# VFD_LCD.net
KiCad netlist of a schematic drawn in Altium Designer
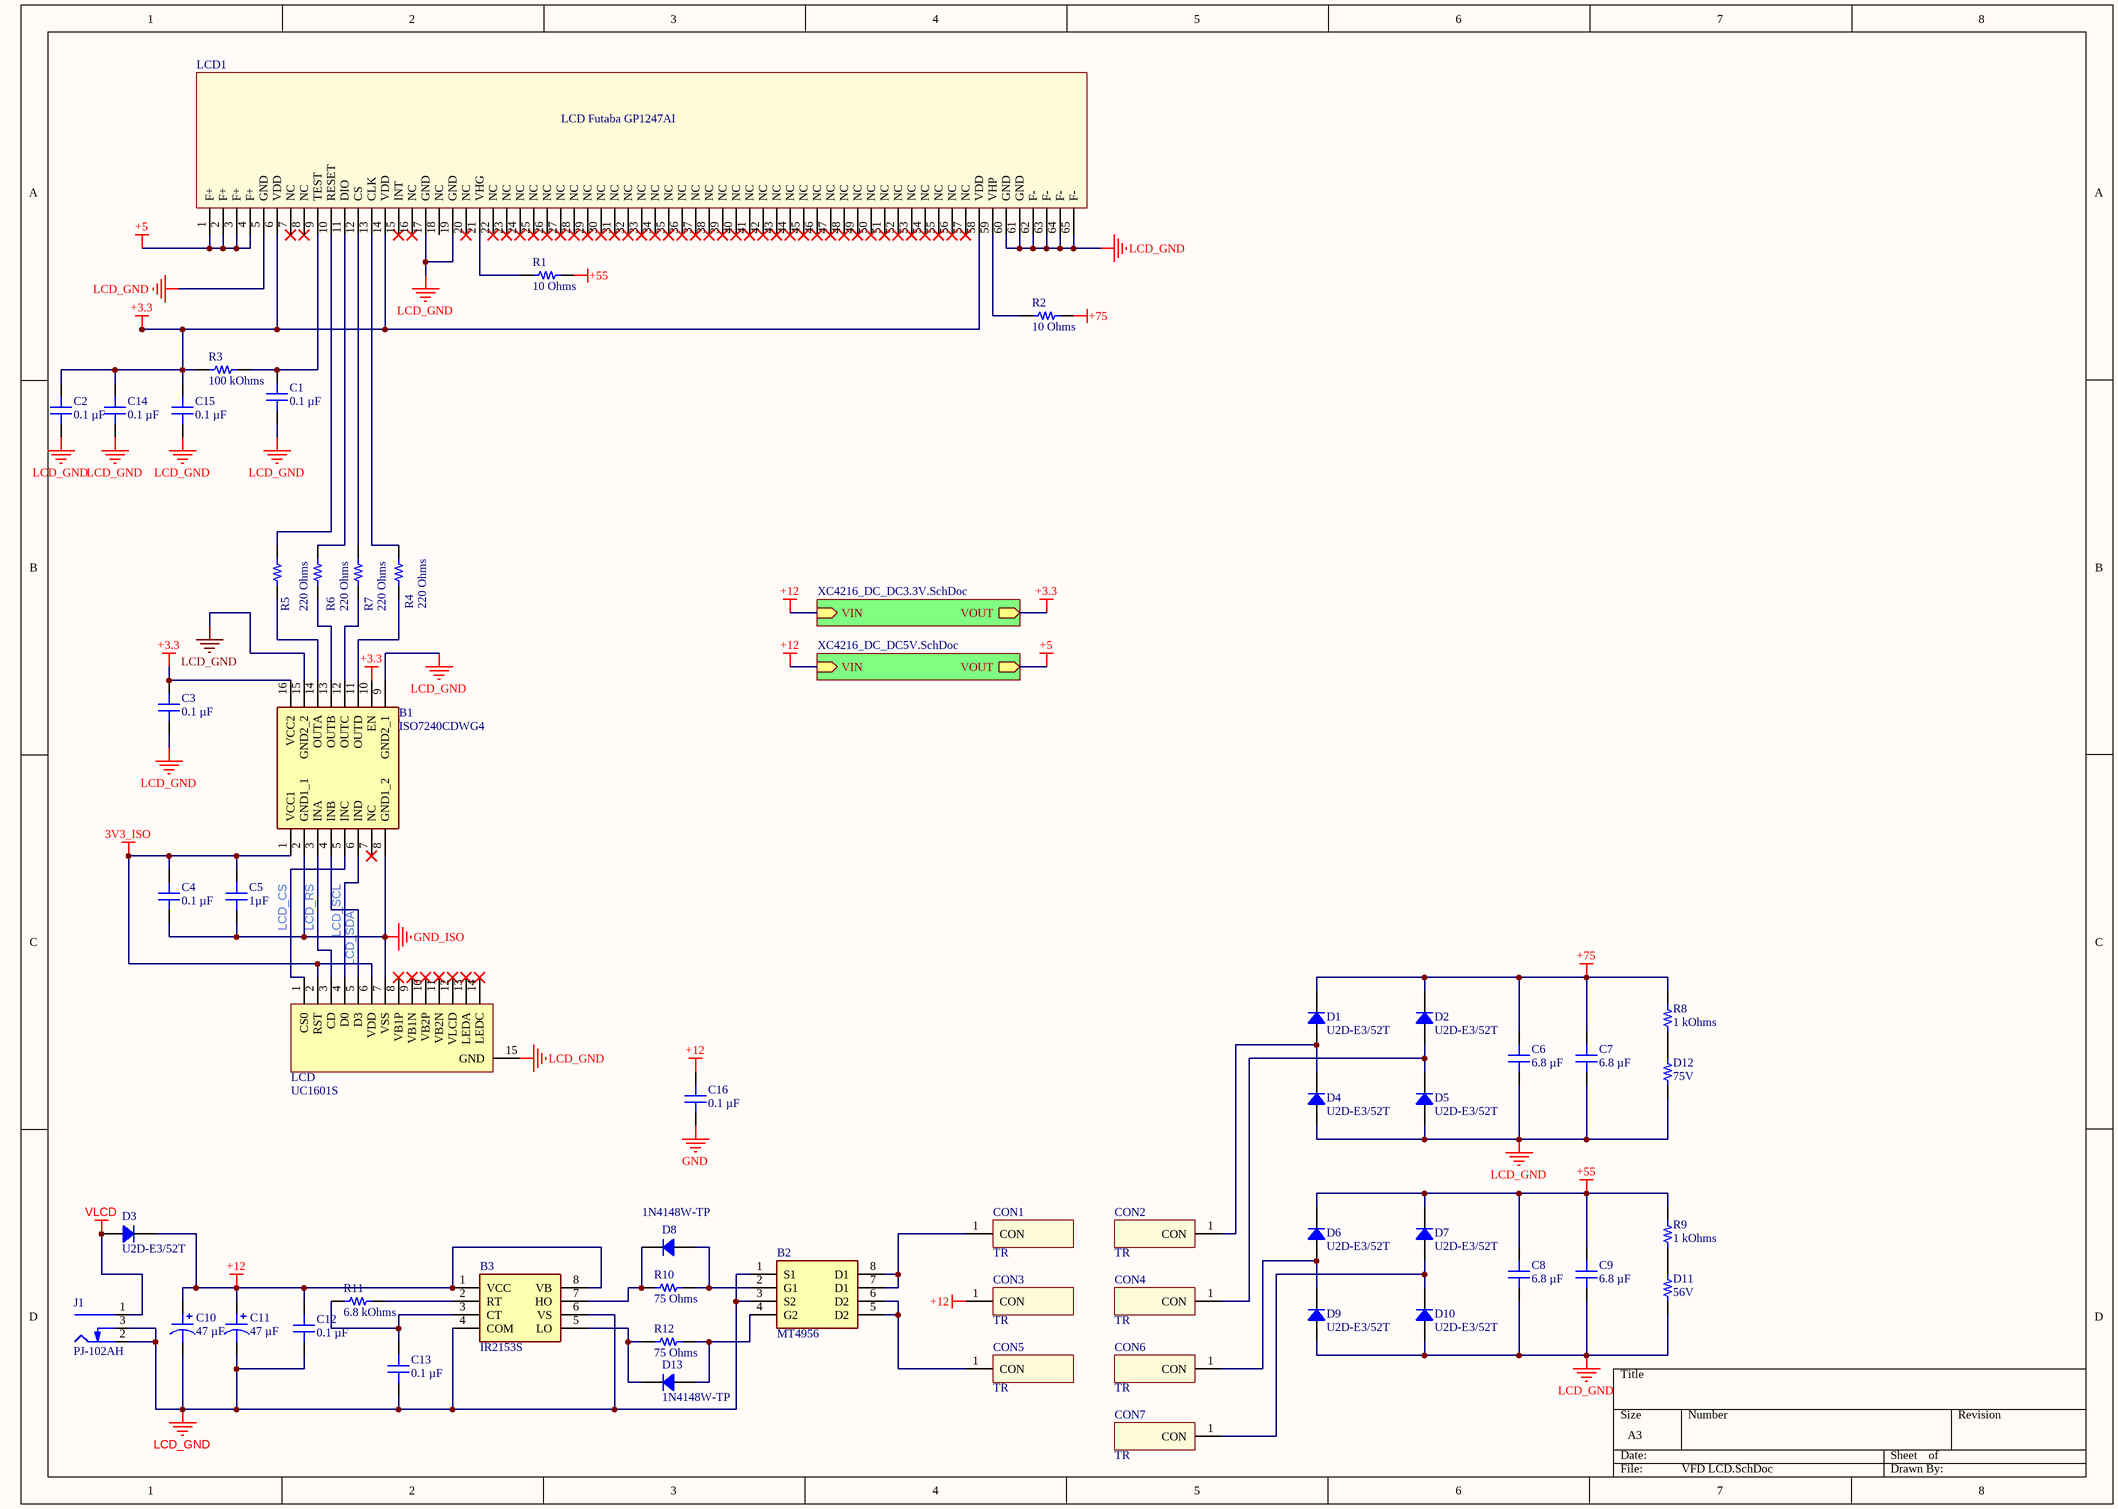
[diagram p0: VFD LCD.SchDoc]

(export (version "E")
  (design (tool "Eeschema 10.0.6"))
  (components
    (comp (ref "B1")
      (value "ISO7240CDWG4")
      (footprint "SOIC127P1030X265-16N")
      (description "Digital Isolator CMOS 4-CH 25Mbps 16-Pin SOIC Tube")
      (fields (field (name "MOUSER PART NUMBER") "595-ISO7240CDWG4"))
      (libsource (lib "My altlib") (part "ISO7240CDWG4"))
    )
    (comp (ref "B2")
      (value "MT4956")
      (footprint "SOIC127P600X175-8N")
      (description "N-Channel PowerTrench® MOSFET\r\n60V, 5A, mΩ")
      (fields (field (name "MANUFACTURER_PART_NUMBER") "IR2153S"))
      (libsource (lib "My altlib") (part "MT4956"))
    )
    (comp (ref "B3")
      (value "IR2153S")
      (footprint "SOIC127P600X175-8N")
      (libsource (lib "My altlib") (part "IR2153S"))
    )
    (comp (ref "C1")
      (value "0.1 µF")
      (footprint "CAP 0805_2012")
      (description "CAP CER 0.1UF 50V X7R 0805")
      (fields (field (name "PART NUMBER") "CC0805MRX7R9BB104") (field (name "MANUFACTURER") "Yageo"))
      (libsource (lib "Celestial Altium Library - altium_library") (part "Capacitor"))
    )
    (comp (ref "C2")
      (value "0.1 µF")
      (footprint "CAP 0805_2012")
      (description "CAP CER 0.1UF 50V X7R 0805")
      (fields (field (name "PART NUMBER") "CC0805MRX7R9BB104") (field (name "MANUFACTURER") "Yageo"))
      (libsource (lib "Celestial Altium Library - altium_library") (part "Capacitor"))
    )
    (comp (ref "C3")
      (value "0.1 µF")
      (footprint "CAP 0805_2012")
      (description "CAP CER 0.1UF 50V X7R 0805")
      (fields (field (name "PART NUMBER") "CC0805MRX7R9BB104") (field (name "MANUFACTURER") "Yageo"))
      (libsource (lib "Celestial Altium Library - altium_library") (part "Capacitor"))
    )
    (comp (ref "C4")
      (value "0.1 µF")
      (footprint "CAP 0805_2012")
      (description "CAP CER 0.1UF 50V X7R 0805")
      (fields (field (name "PART NUMBER") "CC0805MRX7R9BB104") (field (name "MANUFACTURER") "Yageo"))
      (libsource (lib "Celestial Altium Library - altium_library") (part "Capacitor"))
    )
    (comp (ref "C5")
      (value "1µF")
      (footprint "CAP 0805_2012")
      (description "CAP CER 1UF 10V X7R 0805")
      (fields (field (name "PART NUMBER") "MM05ZC105KCZ2A") (field (name "MANUFACTURER") "AVX Corporation"))
      (libsource (lib "Celestial Altium Library - altium_library") (part "Capacitor"))
    )
    (comp (ref "C6")
      (value "6.8 µF")
      (footprint "CAP 1210_3225 - 1MM")
      (description "CAP CER 6.8UF 50V X7S 1210")
      (fields
        (field (name "PART NUMBER") "CGA6P3X7S1H685K250AB")
        (field (name "MANUFACTURER") "TDK Corporation")
      )
      (libsource (lib "Celestial Altium Library - altium_library") (part "Capacitor"))
    )
    (comp (ref "C7")
      (value "6.8 µF")
      (footprint "CAP 1210_3225 - 1MM")
      (description "CAP CER 6.8UF 50V X7S 1210")
      (fields
        (field (name "PART NUMBER") "CGA6P3X7S1H685K250AB")
        (field (name "MANUFACTURER") "TDK Corporation")
      )
      (libsource (lib "Celestial Altium Library - altium_library") (part "Capacitor"))
    )
    (comp (ref "C8")
      (value "6.8 µF")
      (footprint "CAP 1210_3225 - 1MM")
      (description "CAP CER 6.8UF 50V X7S 1210")
      (fields
        (field (name "PART NUMBER") "CGA6P3X7S1H685K250AB")
        (field (name "MANUFACTURER") "TDK Corporation")
      )
      (libsource (lib "Celestial Altium Library - altium_library") (part "Capacitor"))
    )
    (comp (ref "C9")
      (value "6.8 µF")
      (footprint "CAP 1210_3225 - 1MM")
      (description "CAP CER 6.8UF 50V X7S 1210")
      (fields
        (field (name "PART NUMBER") "CGA6P3X7S1H685K250AB")
        (field (name "MANUFACTURER") "TDK Corporation")
      )
      (libsource (lib "Celestial Altium Library - altium_library") (part "Capacitor"))
    )
    (comp (ref "C10")
      (value "47 µF")
      (footprint "CAP ALSMD 8.3MM H10.5MM")
      (description "CAP ALUM 47UF 20% 63V SMD")
      (fields (field (name "PART NUMBER") "63SGV47M8X10.5") (field (name "MANUFACTURER") "Rubycon"))
      (libsource (lib "Celestial Altium Library - altium_library") (part "Polarised Capacitor"))
    )
    (comp (ref "C11")
      (value "47 µF")
      (footprint "CAP ALSMD 8.3MM H10.5MM")
      (description "CAP ALUM 47UF 20% 63V SMD")
      (fields (field (name "PART NUMBER") "63SGV47M8X10.5") (field (name "MANUFACTURER") "Rubycon"))
      (libsource (lib "Celestial Altium Library - altium_library") (part "Polarised Capacitor"))
    )
    (comp (ref "C12")
      (value "0.1 µF")
      (footprint "CAP 1206_3216 - 0.8MM")
      (description "CAP CER 0.1UF 50V Y5V 1206")
      (fields (field (name "PART NUMBER") "CC1206MRY5V9BB104") (field (name "MANUFACTURER") "Yageo"))
      (libsource (lib "Celestial Altium Library - altium_library") (part "Capacitor"))
    )
    (comp (ref "C13")
      (value "0.1 µF")
      (footprint "CAP 1206_3216 - 0.8MM")
      (description "CAP CER 0.1UF 50V Y5V 1206")
      (fields (field (name "PART NUMBER") "CC1206MRY5V9BB104") (field (name "MANUFACTURER") "Yageo"))
      (libsource (lib "Celestial Altium Library - altium_library") (part "Capacitor"))
    )
    (comp (ref "C14")
      (value "0.1 µF")
      (footprint "CAP 0805_2012")
      (description "CAP CER 0.1UF 50V X7R 0805")
      (fields (field (name "PART NUMBER") "CC0805MRX7R9BB104") (field (name "MANUFACTURER") "Yageo"))
      (libsource (lib "Celestial Altium Library - altium_library") (part "Capacitor"))
    )
    (comp (ref "C15")
      (value "0.1 µF")
      (footprint "CAP 0805_2012")
      (description "CAP CER 0.1UF 50V X7R 0805")
      (fields (field (name "PART NUMBER") "CC0805MRX7R9BB104") (field (name "MANUFACTURER") "Yageo"))
      (libsource (lib "Celestial Altium Library - altium_library") (part "Capacitor"))
    )
    (comp (ref "C16")
      (value "0.1 µF")
      (footprint "CAP 1206_3216 - 0.8MM")
      (description "CAP CER 0.1UF 50V Y5V 1206")
      (fields (field (name "PART NUMBER") "CC1206MRY5V9BB104") (field (name "MANUFACTURER") "Yageo"))
      (libsource (lib "Celestial Altium Library - altium_library") (part "Capacitor"))
    )
    (comp (ref "CON1")
      (value "TR")
      (footprint "one contact 0,8_1.6")
      (description "ONE_Contact")
      (libsource (lib "") (part "ONE_Contact_1"))
    )
    (comp (ref "CON2")
      (value "TR")
      (footprint "one contact 0,8_1.6")
      (description "ONE_Contact")
      (libsource (lib "My altlib") (part "ONE_Contact"))
    )
    (comp (ref "CON3")
      (value "TR")
      (footprint "one contact 0,8_1.6")
      (description "ONE_Contact")
      (libsource (lib "") (part "ONE_Contact_1"))
    )
    (comp (ref "CON4")
      (value "TR")
      (footprint "one contact 0,8_1.6")
      (description "ONE_Contact")
      (libsource (lib "My altlib") (part "ONE_Contact"))
    )
    (comp (ref "CON5")
      (value "TR")
      (footprint "one contact 0,8_1.6")
      (description "ONE_Contact")
      (libsource (lib "") (part "ONE_Contact_1"))
    )
    (comp (ref "CON6")
      (value "TR")
      (footprint "one contact 0,8_1.6")
      (description "ONE_Contact")
      (libsource (lib "My altlib") (part "ONE_Contact"))
    )
    (comp (ref "CON7")
      (value "TR")
      (footprint "one contact 0,8_1.6")
      (description "ONE_Contact")
      (libsource (lib "My altlib") (part "ONE_Contact"))
    )
    (comp (ref "D1")
      (value "U2D-E3/52T")
      (footprint "DO214AA SMB")
      (description "DIODE GEN PURP 200V 2A DO214AA")
      (fields (field (name "MANUFACTURER") "Vishay Semiconductor Diodes Division"))
      (libsource (lib "Celestial Altium Library - altium_library") (part "Diode"))
    )
    (comp (ref "D2")
      (value "U2D-E3/52T")
      (footprint "DO214AA SMB")
      (description "DIODE GEN PURP 200V 2A DO214AA")
      (fields (field (name "MANUFACTURER") "Vishay Semiconductor Diodes Division"))
      (libsource (lib "Celestial Altium Library - altium_library") (part "Diode"))
    )
    (comp (ref "D3")
      (value "U2D-E3/52T")
      (footprint "DO214AA SMB")
      (description "DIODE GEN PURP 200V 2A DO214AA")
      (fields (field (name "MANUFACTURER") "Vishay Semiconductor Diodes Division"))
      (libsource (lib "Celestial Altium Library - altium_library") (part "Diode"))
    )
    (comp (ref "D4")
      (value "U2D-E3/52T")
      (footprint "DO214AA SMB")
      (description "DIODE GEN PURP 200V 2A DO214AA")
      (fields (field (name "MANUFACTURER") "Vishay Semiconductor Diodes Division"))
      (libsource (lib "Celestial Altium Library - altium_library") (part "Diode"))
    )
    (comp (ref "D5")
      (value "U2D-E3/52T")
      (footprint "DO214AA SMB")
      (description "DIODE GEN PURP 200V 2A DO214AA")
      (fields (field (name "MANUFACTURER") "Vishay Semiconductor Diodes Division"))
      (libsource (lib "Celestial Altium Library - altium_library") (part "Diode"))
    )
    (comp (ref "D6")
      (value "U2D-E3/52T")
      (footprint "DO214AA SMB")
      (description "DIODE GEN PURP 200V 2A DO214AA")
      (fields (field (name "MANUFACTURER") "Vishay Semiconductor Diodes Division"))
      (libsource (lib "Celestial Altium Library - altium_library") (part "Diode"))
    )
    (comp (ref "D7")
      (value "U2D-E3/52T")
      (footprint "DO214AA SMB")
      (description "DIODE GEN PURP 200V 2A DO214AA")
      (fields (field (name "MANUFACTURER") "Vishay Semiconductor Diodes Division"))
      (libsource (lib "Celestial Altium Library - altium_library") (part "Diode"))
    )
    (comp (ref "D8")
      (value "1N4148W-TP")
      (footprint "SOD-123")
      (description "DIODE GEN PURP 100V 150MA SOD123")
      (fields (field (name "MANUFACTURER") "Micro Commercial Co"))
      (libsource (lib "Celestial Altium Library - altium_library") (part "Diode"))
    )
    (comp (ref "D9")
      (value "U2D-E3/52T")
      (footprint "DO214AA SMB")
      (description "DIODE GEN PURP 200V 2A DO214AA")
      (fields (field (name "MANUFACTURER") "Vishay Semiconductor Diodes Division"))
      (libsource (lib "Celestial Altium Library - altium_library") (part "Diode"))
    )
    (comp (ref "D10")
      (value "U2D-E3/52T")
      (footprint "DO214AA SMB")
      (description "DIODE GEN PURP 200V 2A DO214AA")
      (fields (field (name "MANUFACTURER") "Vishay Semiconductor Diodes Division"))
      (libsource (lib "Celestial Altium Library - altium_library") (part "Diode"))
    )
    (comp (ref "D11")
      (value "56V")
      (footprint "RES 1206_3216")
      (description "RES 1K OHM 0.1% 1/8W 1206")
      (fields
        (field (name "PART NUMBER") "RNCS1206BKE1K00")
        (field (name "MANUFACTURER") "Stackpole Electronics Inc")
      )
      (libsource (lib "Celestial Altium Library - altium_library") (part "Resistor"))
    )
    (comp (ref "D12")
      (value "75V")
      (footprint "RES 1206_3216")
      (description "RES 1K OHM 0.1% 1/8W 1206")
      (fields
        (field (name "PART NUMBER") "RNCS1206BKE1K00")
        (field (name "MANUFACTURER") "Stackpole Electronics Inc")
      )
      (libsource (lib "Celestial Altium Library - altium_library") (part "Resistor"))
    )
    (comp (ref "D13")
      (value "1N4148W-TP")
      (footprint "SOD-123")
      (description "DIODE GEN PURP 100V 150MA SOD123")
      (fields (field (name "MANUFACTURER") "Micro Commercial Co"))
      (libsource (lib "Celestial Altium Library - altium_library") (part "Diode"))
    )
    (comp (ref "J1")
      (value "PJ-102AH")
      (footprint "CUI PJ-102AH")
      (description "CONN PWR JACK 2X5.5MM SOLDER")
      (fields (field (name "MANUFACTURER") "CUI Devices"))
      (libsource (lib "Celestial Altium Library - altium_library") (part "Barrel Connector"))
    )
    (comp (ref "LCD")
      (value "UC1601S")
      (footprint "FPC0514")
      (description "LCD 65*132")
      (libsource (lib "Mylib") (part "UC1601S"))
    )
    (comp (ref "LCD1")
      (value "GP1247AI")
      (footprint "GP1247AI")
      (libsource (lib "My altlib") (part "GP1247AI"))
    )
    (comp (ref "R1")
      (value "10 Ohms")
      (footprint "RES 1206_3216")
      (description "RES 10 OHM 0.1% 1/8W 1206")
      (fields
        (field (name "PART NUMBER") "RNCS1206BKE10R0")
        (field (name "MANUFACTURER") "Stackpole Electronics Inc")
      )
      (libsource (lib "Celestial Altium Library - altium_library") (part "Resistor"))
    )
    (comp (ref "R2")
      (value "10 Ohms")
      (footprint "RES 1206_3216")
      (description "RES 10 OHM 0.1% 1/8W 1206")
      (fields
        (field (name "PART NUMBER") "RNCS1206BKE10R0")
        (field (name "MANUFACTURER") "Stackpole Electronics Inc")
      )
      (libsource (lib "Celestial Altium Library - altium_library") (part "Resistor"))
    )
    (comp (ref "R3")
      (value "100 kOhms")
      (footprint "RES 0805_2012")
      (description "RES SMD 100K OHM 0.1% 1/10W 0805")
      (fields
        (field (name "PART NUMBER") "CPF0805B100KE")
        (field (name "MANUFACTURER") "TE Connectivity Passive Product")
      )
      (libsource (lib "Celestial Altium Library - altium_library") (part "Resistor"))
    )
    (comp (ref "R4")
      (value "220 Ohms")
      (footprint "RES 0805_2012")
      (description "RES 220 OHM 1% 1/3W 0805")
      (fields
        (field (name "PART NUMBER") "CRGP0805F220R")
        (field (name "MANUFACTURER") "TE Connectivity Passive Product")
      )
      (libsource (lib "Celestial Altium Library - altium_library") (part "Resistor"))
    )
    (comp (ref "R5")
      (value "220 Ohms")
      (footprint "RES 0805_2012")
      (description "RES 220 OHM 1% 1/3W 0805")
      (fields
        (field (name "PART NUMBER") "CRGP0805F220R")
        (field (name "MANUFACTURER") "TE Connectivity Passive Product")
      )
      (libsource (lib "Celestial Altium Library - altium_library") (part "Resistor"))
    )
    (comp (ref "R6")
      (value "220 Ohms")
      (footprint "RES 0805_2012")
      (description "RES 220 OHM 1% 1/3W 0805")
      (fields
        (field (name "PART NUMBER") "CRGP0805F220R")
        (field (name "MANUFACTURER") "TE Connectivity Passive Product")
      )
      (libsource (lib "Celestial Altium Library - altium_library") (part "Resistor"))
    )
    (comp (ref "R7")
      (value "220 Ohms")
      (footprint "RES 0805_2012")
      (description "RES 220 OHM 1% 1/3W 0805")
      (fields
        (field (name "PART NUMBER") "CRGP0805F220R")
        (field (name "MANUFACTURER") "TE Connectivity Passive Product")
      )
      (libsource (lib "Celestial Altium Library - altium_library") (part "Resistor"))
    )
    (comp (ref "R8")
      (value "1 kOhms")
      (footprint "RES 1206_3216")
      (description "RES 1K OHM 0.1% 1/8W 1206")
      (fields
        (field (name "PART NUMBER") "RNCS1206BKE1K00")
        (field (name "MANUFACTURER") "Stackpole Electronics Inc")
      )
      (libsource (lib "Celestial Altium Library - altium_library") (part "Resistor"))
    )
    (comp (ref "R9")
      (value "1 kOhms")
      (footprint "RES 1206_3216")
      (description "RES 1K OHM 0.1% 1/8W 1206")
      (fields
        (field (name "PART NUMBER") "RNCS1206BKE1K00")
        (field (name "MANUFACTURER") "Stackpole Electronics Inc")
      )
      (libsource (lib "Celestial Altium Library - altium_library") (part "Resistor"))
    )
    (comp (ref "R10")
      (value "75 Ohms")
      (footprint "RES 0805_2012")
      (description "RES SMD 7.5 OHM 0.1% 1/10W 0805")
      (fields
        (field (name "PART NUMBER") "CPF0805B7R5E1")
        (field (name "MANUFACTURER") "TE Connectivity Passive Product")
      )
      (libsource (lib "Celestial Altium Library - altium_library") (part "Resistor"))
    )
    (comp (ref "R11")
      (value "6.8 kOhms")
      (footprint "RES 1206_3216")
      (description "RES SMD 6.8K OHM 0.05% 1/4W 1206")
      (fields
        (field (name "PART NUMBER") "ERA-8ARW682V")
        (field (name "MANUFACTURER") "Panasonic Electronic Components")
      )
      (libsource (lib "Celestial Altium Library - altium_library") (part "Resistor"))
    )
    (comp (ref "R12")
      (value "75 Ohms")
      (footprint "RES 0805_2012")
      (description "RES SMD 7.5 OHM 0.1% 1/10W 0805")
      (fields
        (field (name "PART NUMBER") "CPF0805B7R5E1")
        (field (name "MANUFACTURER") "TE Connectivity Passive Product")
      )
      (libsource (lib "Celestial Altium Library - altium_library") (part "Resistor"))
    )
  )
  (nets
    (net (code "1") (name "+3.3") (class "Default")
      (node (ref "B1") (pin "10") (pinfunction "EN_10") (pintype "passive"))
      (node (ref "B1") (pin "16") (pinfunction "VCC2_16") (pintype "passive"))
      (node (ref "C14") (pin "2") (pinfunction "2_2") (pintype "passive"))
      (node (ref "C15") (pin "2") (pinfunction "2_2") (pintype "passive"))
      (node (ref "C2") (pin "2") (pinfunction "2_2") (pintype "passive"))
      (node (ref "C3") (pin "1") (pinfunction "1_1") (pintype "passive"))
      (node (ref "LCD1") (pin "14") (pinfunction "VDD_14") (pintype "passive"))
      (node (ref "LCD1") (pin "58") (pinfunction "VDD_58") (pintype "passive"))
      (node (ref "LCD1") (pin "6") (pinfunction "VDD_6") (pintype "passive"))
      (node (ref "R3") (pin "1") (pinfunction "1_1") (pintype "passive"))
    )
    (net (code "2") (name "+5") (class "Default")
      (node (ref "LCD1") (pin "1") (pinfunction "F+_1") (pintype "passive"))
      (node (ref "LCD1") (pin "2") (pinfunction "F+_2") (pintype "passive"))
      (node (ref "LCD1") (pin "3") (pinfunction "F+_3") (pintype "passive"))
      (node (ref "LCD1") (pin "4") (pinfunction "F+_4") (pintype "passive"))
    )
    (net (code "3") (name "+12") (class "Default")
      (node (ref "B3") (pin "1") (pinfunction "VCC_1") (pintype "passive"))
      (node (ref "B3") (pin "8") (pinfunction "VB_8") (pintype "passive"))
      (node (ref "C10") (pin "1") (pinfunction "1_1") (pintype "passive"))
      (node (ref "C11") (pin "1") (pinfunction "1_1") (pintype "passive"))
      (node (ref "C12") (pin "2") (pinfunction "2_2") (pintype "passive"))
      (node (ref "C16") (pin "2") (pinfunction "2_2") (pintype "passive"))
      (node (ref "CON3") (pin "1") (pinfunction "CON_1") (pintype "passive"))
      (node (ref "D3") (pin "2") (pinfunction "2_2") (pintype "passive"))
    )
    (net (code "4") (name "+55") (class "Default")
      (node (ref "C8") (pin "2") (pinfunction "2_2") (pintype "passive"))
      (node (ref "C9") (pin "2") (pinfunction "2_2") (pintype "passive"))
      (node (ref "D6") (pin "2") (pinfunction "2_2") (pintype "passive"))
      (node (ref "D7") (pin "2") (pinfunction "2_2") (pintype "passive"))
      (node (ref "R1") (pin "2") (pinfunction "2_2") (pintype "passive"))
      (node (ref "R9") (pin "2") (pinfunction "2_2") (pintype "passive"))
    )
    (net (code "5") (name "+75") (class "Default")
      (node (ref "C6") (pin "2") (pinfunction "2_2") (pintype "passive"))
      (node (ref "C7") (pin "2") (pinfunction "2_2") (pintype "passive"))
      (node (ref "D1") (pin "2") (pinfunction "2_2") (pintype "passive"))
      (node (ref "D2") (pin "2") (pinfunction "2_2") (pintype "passive"))
      (node (ref "R2") (pin "2") (pinfunction "2_2") (pintype "passive"))
      (node (ref "R8") (pin "2") (pinfunction "2_2") (pintype "passive"))
    )
    (net (code "6") (name "/LCD_CS") (class "Default")
      (node (ref "B1") (pin "5") (pinfunction "INC_5") (pintype "passive"))
      (node (ref "LCD") (pin "1") (pinfunction "CS0_1") (pintype "passive"))
    )
    (net (code "7") (name "/LCD_RS") (class "Default")
      (node (ref "B1") (pin "3") (pinfunction "INA_3") (pintype "passive"))
      (node (ref "LCD") (pin "3") (pinfunction "CD_3") (pintype "passive"))
    )
    (net (code "8") (name "/LCD_SCL") (class "Default")
      (node (ref "B1") (pin "6") (pinfunction "IND_6") (pintype "passive"))
      (node (ref "LCD") (pin "4") (pinfunction "D0_4") (pintype "passive"))
    )
    (net (code "9") (name "/LCD_SDA") (class "Default")
      (node (ref "B1") (pin "4") (pinfunction "INB_4") (pintype "passive"))
      (node (ref "LCD") (pin "5") (pinfunction "D3_5") (pintype "passive"))
    )
    (net (code "10") (name "3V3_ISO") (class "Default")
      (node (ref "B1") (pin "1") (pinfunction "VCC1_1") (pintype "passive"))
      (node (ref "C4") (pin "1") (pinfunction "1_1") (pintype "passive"))
      (node (ref "C5") (pin "2") (pinfunction "2_2") (pintype "passive"))
      (node (ref "LCD") (pin "2") (pinfunction "RST_2") (pintype "passive"))
      (node (ref "LCD") (pin "6") (pinfunction "VDD_6") (pintype "passive"))
    )
    (net (code "11") (name "GND") (class "Default")
      (node (ref "C16") (pin "1") (pinfunction "1_1") (pintype "passive"))
    )
    (net (code "12") (name "GND_ISO") (class "Default")
      (node (ref "B1") (pin "2") (pinfunction "GND1_1_2") (pintype "passive"))
      (node (ref "B1") (pin "8") (pinfunction "GND1_2_8") (pintype "passive"))
      (node (ref "C4") (pin "2") (pinfunction "2_2") (pintype "passive"))
      (node (ref "C5") (pin "1") (pinfunction "1_1") (pintype "passive"))
      (node (ref "LCD") (pin "7") (pinfunction "VSS_7") (pintype "passive"))
    )
    (net (code "13") (name "LCD_GND") (class "Default")
      (node (ref "B1") (pin "15") (pinfunction "GND2_2_15") (pintype "passive"))
      (node (ref "B1") (pin "9") (pinfunction "GND2_1_9") (pintype "passive"))
      (node (ref "B2") (pin "1") (pinfunction "S1_1") (pintype "passive"))
      (node (ref "B2") (pin "3") (pinfunction "S2_3") (pintype "passive"))
      (node (ref "B3") (pin "4") (pinfunction "COM_4") (pintype "passive"))
      (node (ref "B3") (pin "6") (pinfunction "VS_6") (pintype "passive"))
      (node (ref "C1") (pin "1") (pinfunction "1_1") (pintype "passive"))
      (node (ref "C10") (pin "2") (pinfunction "2_2") (pintype "passive"))
      (node (ref "C11") (pin "2") (pinfunction "2_2") (pintype "passive"))
      (node (ref "C12") (pin "1") (pinfunction "1_1") (pintype "passive"))
      (node (ref "C13") (pin "1") (pinfunction "1_1") (pintype "passive"))
      (node (ref "C14") (pin "1") (pinfunction "1_1") (pintype "passive"))
      (node (ref "C15") (pin "1") (pinfunction "1_1") (pintype "passive"))
      (node (ref "C2") (pin "1") (pinfunction "1_1") (pintype "passive"))
      (node (ref "C3") (pin "2") (pinfunction "2_2") (pintype "passive"))
      (node (ref "C6") (pin "1") (pinfunction "1_1") (pintype "passive"))
      (node (ref "C7") (pin "1") (pinfunction "1_1") (pintype "passive"))
      (node (ref "C8") (pin "1") (pinfunction "1_1") (pintype "passive"))
      (node (ref "C9") (pin "1") (pinfunction "1_1") (pintype "passive"))
      (node (ref "D10") (pin "1") (pinfunction "1_1") (pintype "passive"))
      (node (ref "D11") (pin "1") (pinfunction "1_1") (pintype "passive"))
      (node (ref "D12") (pin "1") (pinfunction "1_1") (pintype "passive"))
      (node (ref "D4") (pin "1") (pinfunction "1_1") (pintype "passive"))
      (node (ref "D5") (pin "1") (pinfunction "1_1") (pintype "passive"))
      (node (ref "D9") (pin "1") (pinfunction "1_1") (pintype "passive"))
      (node (ref "J1") (pin "2") (pinfunction "Outer_2") (pintype "passive"))
      (node (ref "J1") (pin "3") (pinfunction "SW_3") (pintype "passive"))
      (node (ref "LCD") (pin "15") (pinfunction "GND_15") (pintype "passive"))
      (node (ref "LCD1") (pin "17") (pinfunction "GND_17") (pintype "passive"))
      (node (ref "LCD1") (pin "19") (pinfunction "GND_19") (pintype "passive"))
      (node (ref "LCD1") (pin "5") (pinfunction "GND_5") (pintype "passive"))
      (node (ref "LCD1") (pin "60") (pinfunction "GND_60") (pintype "passive"))
      (node (ref "LCD1") (pin "61") (pinfunction "GND_61") (pintype "passive"))
      (node (ref "LCD1") (pin "62") (pinfunction "F-_62") (pintype "passive"))
      (node (ref "LCD1") (pin "63") (pinfunction "F-_63") (pintype "passive"))
      (node (ref "LCD1") (pin "64") (pinfunction "F-_64") (pintype "passive"))
      (node (ref "LCD1") (pin "65") (pinfunction "F-_65") (pintype "passive"))
    )
    (net (code "14") (name "Net-(B1-OUTA)") (class "Default")
      (node (ref "B1") (pin "14") (pinfunction "OUTA_14") (pintype "passive"))
      (node (ref "R5") (pin "1") (pinfunction "1_1") (pintype "passive"))
    )
    (net (code "15") (name "Net-(B1-OUTB)") (class "Default")
      (node (ref "B1") (pin "13") (pinfunction "OUTB_13") (pintype "passive"))
      (node (ref "R6") (pin "1") (pinfunction "1_1") (pintype "passive"))
    )
    (net (code "16") (name "Net-(B1-OUTC)") (class "Default")
      (node (ref "B1") (pin "12") (pinfunction "OUTC_12") (pintype "passive"))
      (node (ref "R7") (pin "1") (pinfunction "1_1") (pintype "passive"))
    )
    (net (code "17") (name "Net-(B1-OUTD)") (class "Default")
      (node (ref "B1") (pin "11") (pinfunction "OUTD_11") (pintype "passive"))
      (node (ref "R4") (pin "1") (pinfunction "1_1") (pintype "passive"))
    )
    (net (code "18") (name "Net-(B2-G1)") (class "Default")
      (node (ref "B2") (pin "2") (pinfunction "G1_2") (pintype "passive"))
      (node (ref "D8") (pin "1") (pinfunction "1_1") (pintype "passive"))
      (node (ref "R10") (pin "2") (pinfunction "2_2") (pintype "passive"))
    )
    (net (code "19") (name "Net-(B2-G2)") (class "Default")
      (node (ref "B2") (pin "4") (pinfunction "G2_4") (pintype "passive"))
      (node (ref "D13") (pin "1") (pinfunction "1_1") (pintype "passive"))
      (node (ref "R12") (pin "2") (pinfunction "2_2") (pintype "passive"))
    )
    (net (code "20") (name "Net-(B3-CT)") (class "Default")
      (node (ref "B3") (pin "3") (pinfunction "CT_3") (pintype "passive"))
      (node (ref "C13") (pin "2") (pinfunction "2_2") (pintype "passive"))
      (node (ref "R11") (pin "1") (pinfunction "1_1") (pintype "passive"))
    )
    (net (code "21") (name "Net-(B3-HO)") (class "Default")
      (node (ref "B3") (pin "7") (pinfunction "HO_7") (pintype "passive"))
      (node (ref "D8") (pin "2") (pinfunction "2_2") (pintype "passive"))
      (node (ref "R10") (pin "1") (pinfunction "1_1") (pintype "passive"))
    )
    (net (code "22") (name "Net-(B3-LO)") (class "Default")
      (node (ref "B3") (pin "5") (pinfunction "LO_5") (pintype "passive"))
      (node (ref "D13") (pin "2") (pinfunction "2_2") (pintype "passive"))
      (node (ref "R12") (pin "1") (pinfunction "1_1") (pintype "passive"))
    )
    (net (code "23") (name "Net-(B3-RT)") (class "Default")
      (node (ref "B3") (pin "2") (pinfunction "RT_2") (pintype "passive"))
      (node (ref "R11") (pin "2") (pinfunction "2_2") (pintype "passive"))
    )
    (net (code "24") (name "Net-(CON1-CON)") (class "Default")
      (node (ref "B2") (pin "7") (pinfunction "D1_7") (pintype "passive"))
      (node (ref "B2") (pin "8") (pinfunction "D1_8") (pintype "passive"))
      (node (ref "CON1") (pin "1") (pinfunction "CON_1") (pintype "passive"))
    )
    (net (code "25") (name "Net-(CON2-CON)") (class "Default")
      (node (ref "CON2") (pin "1") (pinfunction "CON_1") (pintype "passive"))
      (node (ref "D1") (pin "1") (pinfunction "1_1") (pintype "passive"))
      (node (ref "D4") (pin "2") (pinfunction "2_2") (pintype "passive"))
    )
    (net (code "26") (name "Net-(CON4-CON)") (class "Default")
      (node (ref "CON4") (pin "1") (pinfunction "CON_1") (pintype "passive"))
      (node (ref "D2") (pin "1") (pinfunction "1_1") (pintype "passive"))
      (node (ref "D5") (pin "2") (pinfunction "2_2") (pintype "passive"))
    )
    (net (code "27") (name "Net-(CON5-CON)") (class "Default")
      (node (ref "B2") (pin "5") (pinfunction "D2_5") (pintype "passive"))
      (node (ref "B2") (pin "6") (pinfunction "D2_6") (pintype "passive"))
      (node (ref "CON5") (pin "1") (pinfunction "CON_1") (pintype "passive"))
    )
    (net (code "28") (name "Net-(CON6-CON)") (class "Default")
      (node (ref "CON6") (pin "1") (pinfunction "CON_1") (pintype "passive"))
      (node (ref "D6") (pin "1") (pinfunction "1_1") (pintype "passive"))
      (node (ref "D9") (pin "2") (pinfunction "2_2") (pintype "passive"))
    )
    (net (code "29") (name "Net-(CON7-CON)") (class "Default")
      (node (ref "CON7") (pin "1") (pinfunction "CON_1") (pintype "passive"))
      (node (ref "D10") (pin "2") (pinfunction "2_2") (pintype "passive"))
      (node (ref "D7") (pin "1") (pinfunction "1_1") (pintype "passive"))
    )
    (net (code "30") (name "Net-(D11-Pad2)") (class "Default")
      (node (ref "D11") (pin "2") (pinfunction "2_2") (pintype "passive"))
      (node (ref "R9") (pin "1") (pinfunction "1_1") (pintype "passive"))
    )
    (net (code "31") (name "Net-(D12-Pad2)") (class "Default")
      (node (ref "D12") (pin "2") (pinfunction "2_2") (pintype "passive"))
      (node (ref "R8") (pin "1") (pinfunction "1_1") (pintype "passive"))
    )
    (net (code "32") (name "Net-(LCD1-CLK)") (class "Default")
      (node (ref "LCD1") (pin "13") (pinfunction "CLK_13") (pintype "passive"))
      (node (ref "R4") (pin "2") (pinfunction "2_2") (pintype "passive"))
    )
    (net (code "33") (name "Net-(LCD1-CS)") (class "Default")
      (node (ref "LCD1") (pin "12") (pinfunction "CS_12") (pintype "passive"))
      (node (ref "R7") (pin "2") (pinfunction "2_2") (pintype "passive"))
    )
    (net (code "34") (name "Net-(LCD1-DIO)") (class "Default")
      (node (ref "LCD1") (pin "11") (pinfunction "DIO_11") (pintype "passive"))
      (node (ref "R6") (pin "2") (pinfunction "2_2") (pintype "passive"))
    )
    (net (code "35") (name "Net-(LCD1-RESET)") (class "Default")
      (node (ref "LCD1") (pin "10") (pinfunction "RESET_10") (pintype "passive"))
      (node (ref "R5") (pin "2") (pinfunction "2_2") (pintype "passive"))
    )
    (net (code "36") (name "Net-(LCD1-TEST)") (class "Default")
      (node (ref "C1") (pin "2") (pinfunction "2_2") (pintype "passive"))
      (node (ref "LCD1") (pin "9") (pinfunction "TEST_9") (pintype "passive"))
      (node (ref "R3") (pin "2") (pinfunction "2_2") (pintype "passive"))
    )
    (net (code "37") (name "Net-(LCD1-VHG)") (class "Default")
      (node (ref "LCD1") (pin "21") (pinfunction "VHG_21") (pintype "passive"))
      (node (ref "R1") (pin "1") (pinfunction "1_1") (pintype "passive"))
    )
    (net (code "38") (name "Net-(LCD1-VHP)") (class "Default")
      (node (ref "LCD1") (pin "59") (pinfunction "VHP_59") (pintype "passive"))
      (node (ref "R2") (pin "1") (pinfunction "1_1") (pintype "passive"))
    )
    (net (code "39") (name "VLCD") (class "Default")
      (node (ref "D3") (pin "1") (pinfunction "1_1") (pintype "passive"))
      (node (ref "J1") (pin "1") (pinfunction "Centre_1") (pintype "passive"))
    )
    (net (code "40") (name "unconnected-(B1-NC-Pad7)") (class "Default")
      (node (ref "B1") (pin "7") (pinfunction "NC_7") (pintype "passive+no_connect"))
    )
    (net (code "41") (name "unconnected-(LCD-LEDA-Pad13)") (class "Default")
      (node (ref "LCD") (pin "13") (pinfunction "LEDA_13") (pintype "passive+no_connect"))
    )
    (net (code "42") (name "unconnected-(LCD-LEDC-Pad14)") (class "Default")
      (node (ref "LCD") (pin "14") (pinfunction "LEDC_14") (pintype "passive+no_connect"))
    )
    (net (code "43") (name "unconnected-(LCD-VB1N-Pad9)") (class "Default")
      (node (ref "LCD") (pin "9") (pinfunction "VB1N_9") (pintype "passive+no_connect"))
    )
    (net (code "44") (name "unconnected-(LCD-VB1P-Pad8)") (class "Default")
      (node (ref "LCD") (pin "8") (pinfunction "VB1P_8") (pintype "passive+no_connect"))
    )
    (net (code "45") (name "unconnected-(LCD-VB2N-Pad11)") (class "Default")
      (node (ref "LCD") (pin "11") (pinfunction "VB2N_11") (pintype "passive+no_connect"))
    )
    (net (code "46") (name "unconnected-(LCD-VB2P-Pad10)") (class "Default")
      (node (ref "LCD") (pin "10") (pinfunction "VB2P_10") (pintype "passive+no_connect"))
    )
    (net (code "47") (name "unconnected-(LCD-VLCD-Pad12)") (class "Default")
      (node (ref "LCD") (pin "12") (pinfunction "VLCD_12") (pintype "passive+no_connect"))
    )
    (net (code "48") (name "unconnected-(LCD1-INT-Pad15)") (class "Default")
      (node (ref "LCD1") (pin "15") (pinfunction "INT_15") (pintype "passive+no_connect"))
    )
    (net (code "49") (name "unconnected-(LCD1-NC-Pad7)") (class "Default")
      (node (ref "LCD1") (pin "7") (pinfunction "NC_7") (pintype "passive+no_connect"))
    )
    (net (code "50") (name "unconnected-(LCD1-NC-Pad8)") (class "Default")
      (node (ref "LCD1") (pin "8") (pinfunction "NC_8") (pintype "passive+no_connect"))
    )
    (net (code "51") (name "unconnected-(LCD1-NC-Pad16)") (class "Default")
      (node (ref "LCD1") (pin "16") (pinfunction "NC_16") (pintype "passive+no_connect"))
    )
    (net (code "52") (name "unconnected-(LCD1-NC-Pad18)") (class "Default")
      (node (ref "LCD1") (pin "18") (pinfunction "NC_18") (pintype "passive"))
    )
    (net (code "53") (name "unconnected-(LCD1-NC-Pad20)") (class "Default")
      (node (ref "LCD1") (pin "20") (pinfunction "NC_20") (pintype "passive+no_connect"))
    )
    (net (code "54") (name "unconnected-(LCD1-NC-Pad22)") (class "Default")
      (node (ref "LCD1") (pin "22") (pinfunction "NC_22") (pintype "passive+no_connect"))
    )
    (net (code "55") (name "unconnected-(LCD1-NC-Pad23)") (class "Default")
      (node (ref "LCD1") (pin "23") (pinfunction "NC_23") (pintype "passive+no_connect"))
    )
    (net (code "56") (name "unconnected-(LCD1-NC-Pad24)") (class "Default")
      (node (ref "LCD1") (pin "24") (pinfunction "NC_24") (pintype "passive+no_connect"))
    )
    (net (code "57") (name "unconnected-(LCD1-NC-Pad25)") (class "Default")
      (node (ref "LCD1") (pin "25") (pinfunction "NC_25") (pintype "passive+no_connect"))
    )
    (net (code "58") (name "unconnected-(LCD1-NC-Pad26)") (class "Default")
      (node (ref "LCD1") (pin "26") (pinfunction "NC_26") (pintype "passive+no_connect"))
    )
    (net (code "59") (name "unconnected-(LCD1-NC-Pad27)") (class "Default")
      (node (ref "LCD1") (pin "27") (pinfunction "NC_27") (pintype "passive+no_connect"))
    )
    (net (code "60") (name "unconnected-(LCD1-NC-Pad28)") (class "Default")
      (node (ref "LCD1") (pin "28") (pinfunction "NC_28") (pintype "passive+no_connect"))
    )
    (net (code "61") (name "unconnected-(LCD1-NC-Pad29)") (class "Default")
      (node (ref "LCD1") (pin "29") (pinfunction "NC_29") (pintype "passive+no_connect"))
    )
    (net (code "62") (name "unconnected-(LCD1-NC-Pad30)") (class "Default")
      (node (ref "LCD1") (pin "30") (pinfunction "NC_30") (pintype "passive+no_connect"))
    )
    (net (code "63") (name "unconnected-(LCD1-NC-Pad31)") (class "Default")
      (node (ref "LCD1") (pin "31") (pinfunction "NC_31") (pintype "passive+no_connect"))
    )
    (net (code "64") (name "unconnected-(LCD1-NC-Pad32)") (class "Default")
      (node (ref "LCD1") (pin "32") (pinfunction "NC_32") (pintype "passive+no_connect"))
    )
    (net (code "65") (name "unconnected-(LCD1-NC-Pad33)") (class "Default")
      (node (ref "LCD1") (pin "33") (pinfunction "NC_33") (pintype "passive+no_connect"))
    )
    (net (code "66") (name "unconnected-(LCD1-NC-Pad34)") (class "Default")
      (node (ref "LCD1") (pin "34") (pinfunction "NC_34") (pintype "passive+no_connect"))
    )
    (net (code "67") (name "unconnected-(LCD1-NC-Pad35)") (class "Default")
      (node (ref "LCD1") (pin "35") (pinfunction "NC_35") (pintype "passive+no_connect"))
    )
    (net (code "68") (name "unconnected-(LCD1-NC-Pad36)") (class "Default")
      (node (ref "LCD1") (pin "36") (pinfunction "NC_36") (pintype "passive+no_connect"))
    )
    (net (code "69") (name "unconnected-(LCD1-NC-Pad37)") (class "Default")
      (node (ref "LCD1") (pin "37") (pinfunction "NC_37") (pintype "passive+no_connect"))
    )
    (net (code "70") (name "unconnected-(LCD1-NC-Pad38)") (class "Default")
      (node (ref "LCD1") (pin "38") (pinfunction "NC_38") (pintype "passive+no_connect"))
    )
    (net (code "71") (name "unconnected-(LCD1-NC-Pad39)") (class "Default")
      (node (ref "LCD1") (pin "39") (pinfunction "NC_39") (pintype "passive+no_connect"))
    )
    (net (code "72") (name "unconnected-(LCD1-NC-Pad40)") (class "Default")
      (node (ref "LCD1") (pin "40") (pinfunction "NC_40") (pintype "passive+no_connect"))
    )
    (net (code "73") (name "unconnected-(LCD1-NC-Pad41)") (class "Default")
      (node (ref "LCD1") (pin "41") (pinfunction "NC_41") (pintype "passive+no_connect"))
    )
    (net (code "74") (name "unconnected-(LCD1-NC-Pad42)") (class "Default")
      (node (ref "LCD1") (pin "42") (pinfunction "NC_42") (pintype "passive+no_connect"))
    )
    (net (code "75") (name "unconnected-(LCD1-NC-Pad43)") (class "Default")
      (node (ref "LCD1") (pin "43") (pinfunction "NC_43") (pintype "passive+no_connect"))
    )
    (net (code "76") (name "unconnected-(LCD1-NC-Pad44)") (class "Default")
      (node (ref "LCD1") (pin "44") (pinfunction "NC_44") (pintype "passive+no_connect"))
    )
    (net (code "77") (name "unconnected-(LCD1-NC-Pad45)") (class "Default")
      (node (ref "LCD1") (pin "45") (pinfunction "NC_45") (pintype "passive+no_connect"))
    )
    (net (code "78") (name "unconnected-(LCD1-NC-Pad46)") (class "Default")
      (node (ref "LCD1") (pin "46") (pinfunction "NC_46") (pintype "passive+no_connect"))
    )
    (net (code "79") (name "unconnected-(LCD1-NC-Pad47)") (class "Default")
      (node (ref "LCD1") (pin "47") (pinfunction "NC_47") (pintype "passive+no_connect"))
    )
    (net (code "80") (name "unconnected-(LCD1-NC-Pad48)") (class "Default")
      (node (ref "LCD1") (pin "48") (pinfunction "NC_48") (pintype "passive+no_connect"))
    )
    (net (code "81") (name "unconnected-(LCD1-NC-Pad49)") (class "Default")
      (node (ref "LCD1") (pin "49") (pinfunction "NC_49") (pintype "passive+no_connect"))
    )
    (net (code "82") (name "unconnected-(LCD1-NC-Pad50)") (class "Default")
      (node (ref "LCD1") (pin "50") (pinfunction "NC_50") (pintype "passive+no_connect"))
    )
    (net (code "83") (name "unconnected-(LCD1-NC-Pad51)") (class "Default")
      (node (ref "LCD1") (pin "51") (pinfunction "NC_51") (pintype "passive+no_connect"))
    )
    (net (code "84") (name "unconnected-(LCD1-NC-Pad52)") (class "Default")
      (node (ref "LCD1") (pin "52") (pinfunction "NC_52") (pintype "passive+no_connect"))
    )
    (net (code "85") (name "unconnected-(LCD1-NC-Pad53)") (class "Default")
      (node (ref "LCD1") (pin "53") (pinfunction "NC_53") (pintype "passive+no_connect"))
    )
    (net (code "86") (name "unconnected-(LCD1-NC-Pad54)") (class "Default")
      (node (ref "LCD1") (pin "54") (pinfunction "NC_54") (pintype "passive+no_connect"))
    )
    (net (code "87") (name "unconnected-(LCD1-NC-Pad55)") (class "Default")
      (node (ref "LCD1") (pin "55") (pinfunction "NC_55") (pintype "passive+no_connect"))
    )
    (net (code "88") (name "unconnected-(LCD1-NC-Pad56)") (class "Default")
      (node (ref "LCD1") (pin "56") (pinfunction "NC_56") (pintype "passive+no_connect"))
    )
    (net (code "89") (name "unconnected-(LCD1-NC-Pad57)") (class "Default")
      (node (ref "LCD1") (pin "57") (pinfunction "NC_57") (pintype "passive+no_connect"))
    )
  )
)
